# RGB_PMOLED_0_6IN.net
KiCad netlist of a schematic drawn in EAGLE
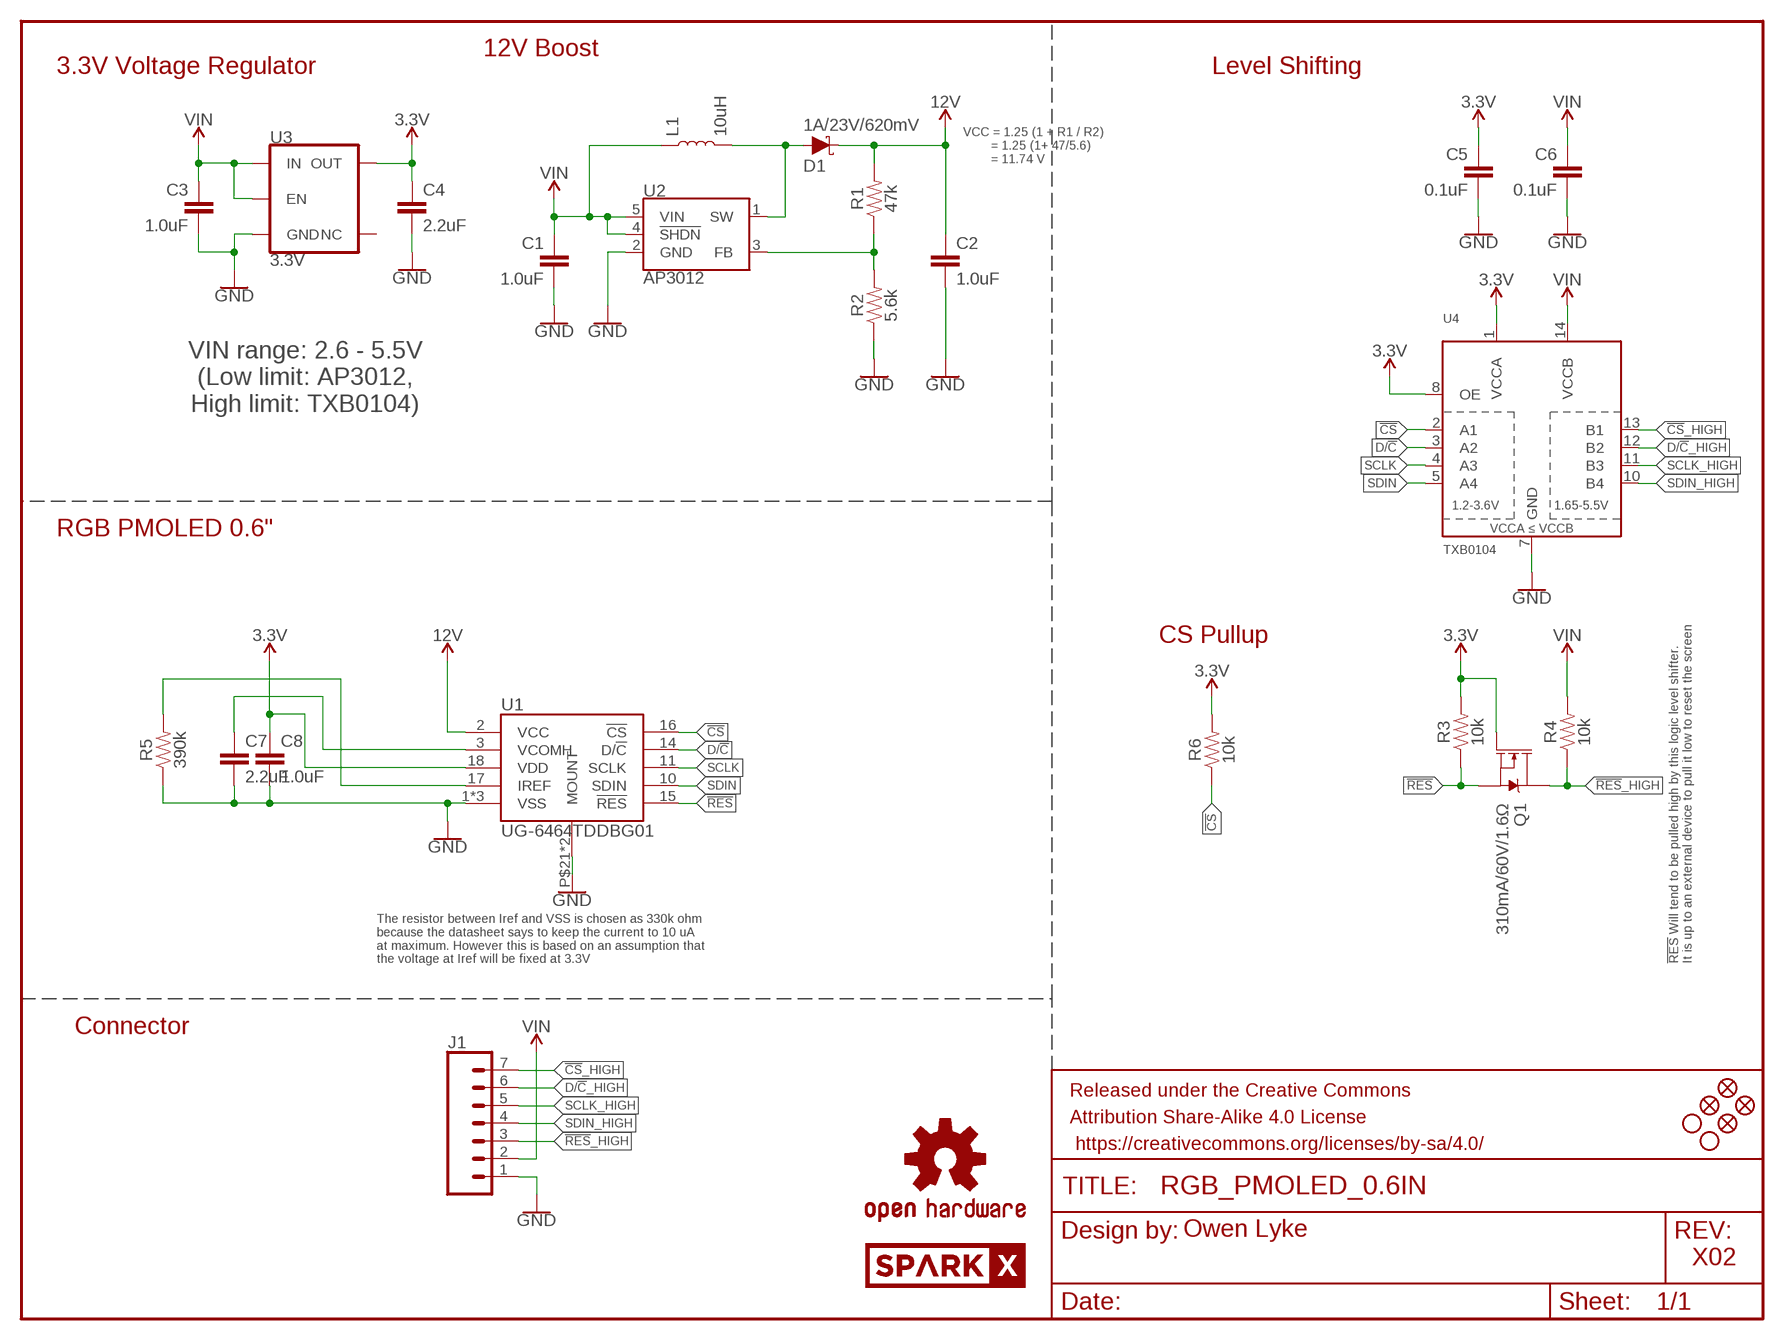
[diagram p0: schematic, sheet 1]

(export (version "E")
  (design (tool "Eeschema 10.0.6"))
  (components
    (comp (ref "C1")
      (value "1.0uF")
      (footprint "eagle-import:0603")
      (libsource (lib "eagle-import") (part "1.0UF-0603-16V-10%"))
    )
    (comp (ref "C2")
      (value "1.0uF")
      (footprint "eagle-import:0603")
      (libsource (lib "eagle-import") (part "1.0UF-0603-16V-10%"))
    )
    (comp (ref "C3")
      (value "1.0uF")
      (footprint "eagle-import:0603")
      (libsource (lib "eagle-import") (part "1.0UF-0603-16V-10%"))
    )
    (comp (ref "C4")
      (value "2.2uF")
      (footprint "eagle-import:0603")
      (libsource (lib "eagle-import") (part "2.2UF-0603-10V-20%"))
    )
    (comp (ref "C5")
      (value "0.1uF")
      (footprint "eagle-import:0603")
      (libsource (lib "eagle-import") (part "0.1UF-0603-25V-(+80/-20%)"))
    )
    (comp (ref "C6")
      (value "0.1uF")
      (footprint "eagle-import:0603")
      (libsource (lib "eagle-import") (part "0.1UF-0603-25V-(+80/-20%)"))
    )
    (comp (ref "C7")
      (value "2.2uF")
      (footprint "eagle-import:0805")
      (libsource (lib "eagle-import") (part "2.2UF-0805-25V-(+80/-20%)"))
    )
    (comp (ref "C8")
      (value "1.0uF")
      (footprint "eagle-import:0603")
      (libsource (lib "eagle-import") (part "1.0UF-0603-16V-10%"))
    )
    (comp (ref "D1")
      (value "1A/23V/620mV")
      (footprint "eagle-import:SOD-323")
      (libsource (lib "eagle-import") (part "DIODE-SCHOTTKY-BAT20J"))
    )
    (comp (ref "FD1")
      (value "FIDUCIAL1X2")
      (footprint "eagle-import:FIDUCIAL-1X2")
      (libsource (lib "eagle-import") (part "FIDUCIAL1X2"))
    )
    (comp (ref "FD2")
      (value "FIDUCIAL1X2")
      (footprint "eagle-import:FIDUCIAL-1X2")
      (libsource (lib "eagle-import") (part "FIDUCIAL1X2"))
    )
    (comp (ref "FD3")
      (value "FIDUCIAL1X2")
      (footprint "eagle-import:FIDUCIAL-1X2")
      (libsource (lib "eagle-import") (part "FIDUCIAL1X2"))
    )
    (comp (ref "FD4")
      (value "FIDUCIAL1X2")
      (footprint "eagle-import:FIDUCIAL-1X2")
      (libsource (lib "eagle-import") (part "FIDUCIAL1X2"))
    )
    (comp (ref "FRAME1")
      (value "FRAME-LETTER")
      (footprint "eagle-import:CREATIVE_COMMONS")
      (libsource (lib "eagle-import") (part "FRAME-LETTER"))
    )
    (comp (ref "H1")
      (value "STAND-OFF")
      (footprint "eagle-import:STAND-OFF")
      (libsource (lib "eagle-import") (part "STAND-OFF"))
    )
    (comp (ref "H2")
      (value "STAND-OFF")
      (footprint "eagle-import:STAND-OFF")
      (libsource (lib "eagle-import") (part "STAND-OFF"))
    )
    (comp (ref "J1")
      (value "CONN_07NO_SILK")
      (footprint "eagle-import:1X07_NO_SILK")
      (libsource (lib "eagle-import") (part "CONN_07NO_SILK"))
    )
    (comp (ref "L1")
      (value "10uH")
      (footprint "eagle-import:INDUCTOR_4.7UH")
      (libsource (lib "eagle-import") (part "INDUCTOR-CDRH-10UH"))
    )
    (comp (ref "LOGO1")
      (value "SPARKX-LOGO5")
      (footprint "eagle-import:SPARKX-LARGE")
      (libsource (lib "eagle-import") (part "SPARKX-LOGO5"))
    )
    (comp (ref "LOGO2")
      (value "OSHW-LOGOS")
      (footprint "eagle-import:OSHW-LOGO-S")
      (libsource (lib "eagle-import") (part "OSHW-LOGOS"))
    )
    (comp (ref "Q1")
      (value "310mA/60V/1.6Ω")
      (footprint "eagle-import:SOT323")
      (libsource (lib "eagle-import") (part "MOSFET-NCH-2N7002PW"))
    )
    (comp (ref "R1")
      (value "47k")
      (footprint "eagle-import:0603")
      (libsource (lib "eagle-import") (part "47KOHM-0603-1/10W-1%"))
    )
    (comp (ref "R2")
      (value "5.6k")
      (footprint "eagle-import:0603")
      (libsource (lib "eagle-import") (part "5.6KOHM-0603-1/10W-1%"))
    )
    (comp (ref "R3")
      (value "10k")
      (footprint "eagle-import:0603")
      (libsource (lib "eagle-import") (part "10KOHM-0603-1/10W-1%"))
    )
    (comp (ref "R4")
      (value "10k")
      (footprint "eagle-import:0603")
      (libsource (lib "eagle-import") (part "10KOHM-0603-1/10W-1%"))
    )
    (comp (ref "R5")
      (value "390k")
      (footprint "eagle-import:0603")
      (libsource (lib "eagle-import") (part "390KOHM-0603-1/10W-1%"))
    )
    (comp (ref "R6")
      (value "10k")
      (footprint "eagle-import:0603")
      (libsource (lib "eagle-import") (part "10KOHM-0603-1/10W-1%"))
    )
    (comp (ref "U1")
      (value "UG-6464TDDBG01")
      (footprint "eagle-import:AMPHENOL_10051922-2010ELF")
      (libsource (lib "eagle-import") (part "UG-6464TDDBG01"))
    )
    (comp (ref "U2")
      (value "AP3012")
      (footprint "eagle-import:SOT23-5")
      (libsource (lib "eagle-import") (part "AP3012"))
    )
    (comp (ref "U3")
      (value "3.3V")
      (footprint "eagle-import:SOT23-5")
      (libsource (lib "eagle-import") (part "V_REG_AP2112K-3.3V"))
    )
    (comp (ref "U4")
      (value "TXB0104")
      (footprint "eagle-import:SO14")
      (libsource (lib "eagle-import") (part "TXB0104PWRSOIC14"))
    )
  )
  (nets
    (net (code "1") (name "/D{slash}~{C}") (class "Default")
      (node (ref "U1") (pin "14") (pinfunction "D/~{C}_14") (pintype "bidirectional"))
      (node (ref "U4") (pin "3") (pinfunction "A2_3") (pintype "bidirectional"))
    )
    (net (code "2") (name "/D{slash}~{C}_HIGH") (class "Default")
      (node (ref "J1") (pin "6") (pinfunction "6_6") (pintype "passive"))
      (node (ref "U4") (pin "12") (pinfunction "B2_12") (pintype "bidirectional"))
    )
    (net (code "3") (name "/~{CS}") (class "Default")
      (node (ref "R6") (pin "1") (pinfunction "1_1") (pintype "passive"))
      (node (ref "U1") (pin "16") (pinfunction "~{CS}_16") (pintype "bidirectional"))
      (node (ref "U4") (pin "2") (pinfunction "A1_2") (pintype "bidirectional"))
    )
    (net (code "4") (name "/~{CS}_HIGH") (class "Default")
      (node (ref "J1") (pin "7") (pinfunction "7_7") (pintype "passive"))
      (node (ref "U4") (pin "13") (pinfunction "B1_13") (pintype "bidirectional"))
    )
    (net (code "5") (name "/~{RES}") (class "Default")
      (node (ref "Q1") (pin "2") (pinfunction "S_2") (pintype "bidirectional"))
      (node (ref "R3") (pin "1") (pinfunction "1_1") (pintype "passive"))
      (node (ref "U1") (pin "15") (pinfunction "~{RES}_15") (pintype "bidirectional"))
    )
    (net (code "6") (name "/~{RES}_HIGH") (class "Default")
      (node (ref "J1") (pin "3") (pinfunction "3_3") (pintype "passive"))
      (node (ref "Q1") (pin "3") (pinfunction "D_3") (pintype "bidirectional"))
      (node (ref "R4") (pin "1") (pinfunction "1_1") (pintype "passive"))
    )
    (net (code "7") (name "3.3V") (class "Default")
      (node (ref "C4") (pin "1") (pinfunction "1_1") (pintype "passive"))
      (node (ref "C5") (pin "1") (pinfunction "1_1") (pintype "passive"))
      (node (ref "C8") (pin "1") (pinfunction "1_1") (pintype "passive"))
      (node (ref "Q1") (pin "1") (pinfunction "G_1") (pintype "bidirectional"))
      (node (ref "R3") (pin "2") (pinfunction "2_2") (pintype "passive"))
      (node (ref "R6") (pin "2") (pinfunction "2_2") (pintype "passive"))
      (node (ref "U1") (pin "18") (pinfunction "VDD_18") (pintype "bidirectional"))
      (node (ref "U3") (pin "5") (pinfunction "OUT_5") (pintype "passive"))
      (node (ref "U4") (pin "1") (pinfunction "VCCA_1") (pintype "bidirectional"))
      (node (ref "U4") (pin "8") (pinfunction "OE_8") (pintype "bidirectional"))
    )
    (net (code "8") (name "12V") (class "Default")
      (node (ref "C2") (pin "1") (pinfunction "1_1") (pintype "passive"))
      (node (ref "D1") (pin "C") (pinfunction "C_C") (pintype "passive"))
      (node (ref "R1") (pin "2") (pinfunction "2_2") (pintype "passive"))
      (node (ref "U1") (pin "2") (pinfunction "VCC_2") (pintype "bidirectional"))
    )
    (net (code "9") (name "GND") (class "Default")
      (node (ref "C1") (pin "2") (pinfunction "2_2") (pintype "passive"))
      (node (ref "C2") (pin "2") (pinfunction "2_2") (pintype "passive"))
      (node (ref "C3") (pin "2") (pinfunction "2_2") (pintype "passive"))
      (node (ref "C4") (pin "2") (pinfunction "2_2") (pintype "passive"))
      (node (ref "C5") (pin "2") (pinfunction "2_2") (pintype "passive"))
      (node (ref "C6") (pin "2") (pinfunction "2_2") (pintype "passive"))
      (node (ref "C7") (pin "2") (pinfunction "2_2") (pintype "passive"))
      (node (ref "C8") (pin "2") (pinfunction "2_2") (pintype "passive"))
      (node (ref "J1") (pin "1") (pinfunction "1_1") (pintype "passive"))
      (node (ref "R2") (pin "1") (pinfunction "1_1") (pintype "passive"))
      (node (ref "R5") (pin "1") (pinfunction "1_1") (pintype "passive"))
      (node (ref "U1") (pin "1") (pinfunction "VSS_1") (pintype "bidirectional"))
      (node (ref "U1") (pin "19") (pinfunction "VSS_19") (pintype "bidirectional"))
      (node (ref "U1") (pin "20") (pinfunction "VSS_20") (pintype "bidirectional"))
      (node (ref "U1") (pin "P$21") (pinfunction "MOUNT_P$21") (pintype "bidirectional"))
      (node (ref "U1") (pin "P$22") (pinfunction "MOUNT_P$22") (pintype "bidirectional"))
      (node (ref "U2") (pin "2") (pinfunction "GND_2") (pintype "bidirectional"))
      (node (ref "U3") (pin "2") (pinfunction "GND_2") (pintype "input"))
      (node (ref "U4") (pin "7") (pinfunction "GND_7") (pintype "bidirectional"))
    )
    (net (code "10") (name "Net-(L1-2)") (class "Default")
      (node (ref "D1") (pin "A") (pinfunction "A_A") (pintype "passive"))
      (node (ref "L1") (pin "P$2") (pinfunction "2_P$2") (pintype "passive"))
      (node (ref "U2") (pin "1") (pinfunction "SW_1") (pintype "bidirectional"))
    )
    (net (code "11") (name "Net-(U1-IREF)") (class "Default")
      (node (ref "R5") (pin "2") (pinfunction "2_2") (pintype "passive"))
      (node (ref "U1") (pin "17") (pinfunction "IREF_17") (pintype "bidirectional"))
    )
    (net (code "12") (name "Net-(U1-VCOMH)") (class "Default")
      (node (ref "C7") (pin "1") (pinfunction "1_1") (pintype "passive"))
      (node (ref "U1") (pin "3") (pinfunction "VCOMH_3") (pintype "bidirectional"))
    )
    (net (code "13") (name "Net-(U2-FB)") (class "Default")
      (node (ref "R1") (pin "1") (pinfunction "1_1") (pintype "passive"))
      (node (ref "R2") (pin "2") (pinfunction "2_2") (pintype "passive"))
      (node (ref "U2") (pin "3") (pinfunction "FB_3") (pintype "bidirectional"))
    )
    (net (code "14") (name "SCLK") (class "Default")
      (node (ref "U1") (pin "11") (pinfunction "SCLK_11") (pintype "bidirectional"))
      (node (ref "U4") (pin "4") (pinfunction "A3_4") (pintype "bidirectional"))
    )
    (net (code "15") (name "SCLK_HIGH") (class "Default")
      (node (ref "J1") (pin "5") (pinfunction "5_5") (pintype "passive"))
      (node (ref "U4") (pin "11") (pinfunction "B3_11") (pintype "bidirectional"))
    )
    (net (code "16") (name "SDIN") (class "Default")
      (node (ref "U1") (pin "10") (pinfunction "SDIN_10") (pintype "bidirectional"))
      (node (ref "U4") (pin "5") (pinfunction "A4_5") (pintype "bidirectional"))
    )
    (net (code "17") (name "SDIN_HIGH") (class "Default")
      (node (ref "J1") (pin "4") (pinfunction "4_4") (pintype "passive"))
      (node (ref "U4") (pin "10") (pinfunction "B4_10") (pintype "bidirectional"))
    )
    (net (code "18") (name "VIN") (class "Default")
      (node (ref "C1") (pin "1") (pinfunction "1_1") (pintype "passive"))
      (node (ref "C3") (pin "1") (pinfunction "1_1") (pintype "passive"))
      (node (ref "C6") (pin "1") (pinfunction "1_1") (pintype "passive"))
      (node (ref "J1") (pin "2") (pinfunction "2_2") (pintype "passive"))
      (node (ref "L1") (pin "P$1") (pinfunction "1_P$1") (pintype "passive"))
      (node (ref "R4") (pin "2") (pinfunction "2_2") (pintype "passive"))
      (node (ref "U2") (pin "4") (pinfunction "~{SHDN}_4") (pintype "bidirectional"))
      (node (ref "U2") (pin "5") (pinfunction "VIN_5") (pintype "bidirectional"))
      (node (ref "U3") (pin "1") (pinfunction "IN_1") (pintype "input"))
      (node (ref "U3") (pin "3") (pinfunction "EN_3") (pintype "input"))
      (node (ref "U4") (pin "14") (pinfunction "VCCB_14") (pintype "bidirectional"))
    )
    (net (code "19") (name "unconnected-(U3-NC-Pad4)") (class "Default")
      (node (ref "U3") (pin "4") (pinfunction "NC_4") (pintype "no_connect"))
    )
  )
)
